# Sheet1.net
KiCad netlist of a schematic drawn in Altium Designer
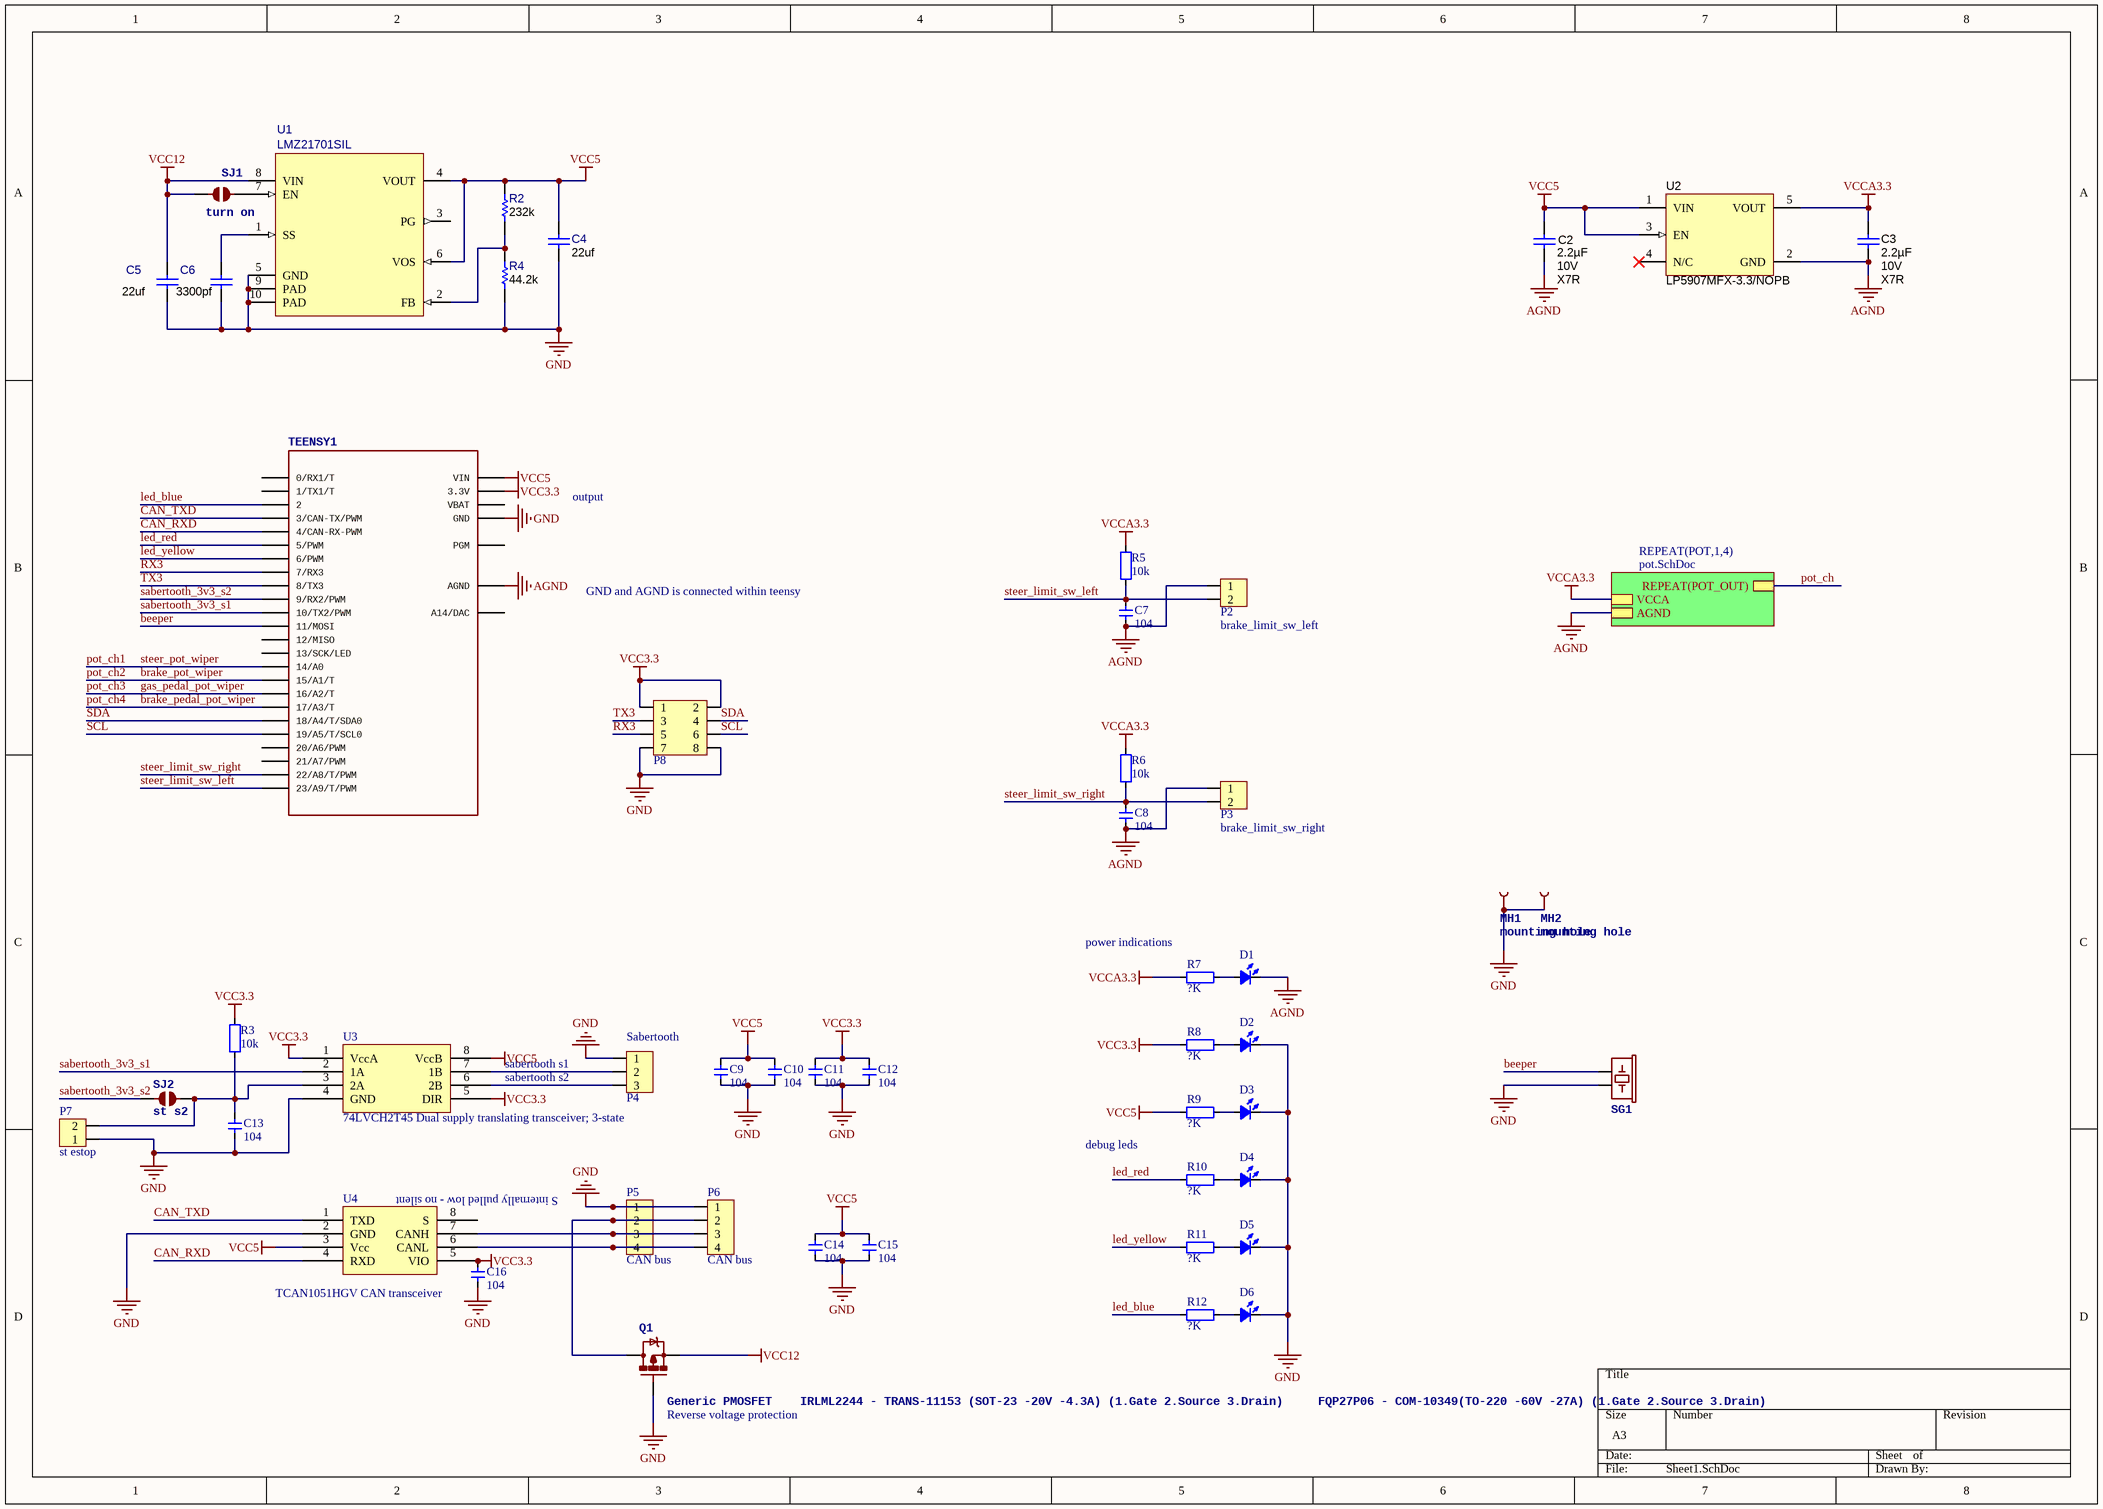
[diagram p0: Sheet1.SchDoc]

(export (version "E")
  (design (tool "Eeschema 10.0.6"))
  (components
    (comp (ref "C2")
      (value "GRM188R71A225KE15D")
      (footprint "PCB_PassiveCap:CAP_0603")
      (description "CAP, CERM, 2.2uF, 10V, +/-10%, X7R, 0603")
      (fields
        (field (name "VALUEDISPLAYED") "2.2µF")
        (field (name "MANUFACTURER") "MuRata")
        (field (name "VALUE2") "10V")
        (field (name "TEMPCO") "X7R")
        (field (name "PUBLISHER") "Texas Instruments")
      )
      (libsource (lib "Capacitor_Ceramic") (part "GRM188R71A225KE15D"))
    )
    (comp (ref "C3")
      (value "GRM188R71A225KE15D")
      (footprint "PCB_PassiveCap:CAP_0603")
      (description "CAP, CERM, 2.2 µF, 10 V, +/- 10%, X7R, 0603")
      (fields
        (field (name "VALUEDISPLAYED") "2.2µF")
        (field (name "MANUFACTURER") "MuRata")
        (field (name "VALUE2") "10V")
        (field (name "TEMPCO") "X7R")
        (field (name "PUBLISHER") "Texas Instruments")
      )
      (libsource (lib "Capacitor_Ceramic") (part "GRM188R71A225KE15D"))
    )
    (comp (ref "C4")
      (value "GRM188R71A225KE15D")
      (footprint "CAP_0805")
      (description "CAP, CERM, 2.2uF, 10V, +/-10%, X7R, 0603")
      (fields
        (field (name "VALUEDISPLAYED") "22uf")
        (field (name "MANUFACTURER") "MuRata")
        (field (name "PUBLISHER") "Texas Instruments")
      )
      (libsource (lib "Capacitor_Ceramic") (part "GRM188R71A225KE15D"))
    )
    (comp (ref "C5")
      (value "GRM155R71E822KA01D")
      (footprint "CAP_0805")
      (description "CAP, CERM, 8200pF, 25V, +/-10%, X7R, 0402")
      (fields
        (field (name "VALUEDISPLAYED") "22uf")
        (field (name "MANUFACTURER") "MuRata")
        (field (name "PUBLISHER") "Texas Instruments")
      )
      (libsource (lib "Capacitor_Ceramic") (part "GRM155R71E822KA01D"))
    )
    (comp (ref "C6")
      (value "GRM155R71E822KA01D")
      (footprint "PCB_PassiveCap:CAP_0603")
      (description "CAP, CERM, 8200pF, 25V, +/-10%, X7R, 0402")
      (fields
        (field (name "VALUEDISPLAYED") "3300pf")
        (field (name "MANUFACTURER") "MuRata")
        (field (name "PUBLISHER") "Texas Instruments")
      )
      (libsource (lib "Capacitor_Ceramic") (part "GRM155R71E822KA01D"))
    )
    (comp (ref "C7")
      (value "104")
      (footprint "PCB_PassiveCap:CAP_0603")
      (description "Capacitor")
      (fields (field (name "Comment") "Cap_0603"))
      (libsource (lib "SCH_Passive") (part "Cap_0603"))
    )
    (comp (ref "C8")
      (value "104")
      (footprint "PCB_PassiveCap:CAP_0603")
      (description "Capacitor")
      (fields (field (name "Comment") "Cap_0603"))
      (libsource (lib "SCH_Passive") (part "Cap_0603"))
    )
    (comp (ref "C9")
      (value "104")
      (footprint "PCB_PassiveCap:CAP_0603")
      (description "Capacitor")
      (fields (field (name "Comment") "Cap_0603"))
      (libsource (lib "SCH_Passive") (part "Cap_0603"))
    )
    (comp (ref "C10")
      (value "104")
      (footprint "PCB_PassiveCap:CAP_0603")
      (description "Capacitor")
      (fields (field (name "Comment") "Cap_0603"))
      (libsource (lib "SCH_Passive") (part "Cap_0603"))
    )
    (comp (ref "C11")
      (value "104")
      (footprint "PCB_PassiveCap:CAP_0603")
      (description "Capacitor")
      (fields (field (name "Comment") "Cap_0603"))
      (libsource (lib "SCH_Passive") (part "Cap_0603"))
    )
    (comp (ref "C12")
      (value "104")
      (footprint "PCB_PassiveCap:CAP_0603")
      (description "Capacitor")
      (fields (field (name "Comment") "Cap_0603"))
      (libsource (lib "SCH_Passive") (part "Cap_0603"))
    )
    (comp (ref "C13")
      (value "104")
      (footprint "PCB_PassiveCap:CAP_0603")
      (description "Capacitor")
      (fields (field (name "Comment") "Cap_0603"))
      (libsource (lib "SCH_Passive") (part "Cap_0603"))
    )
    (comp (ref "C14")
      (value "104")
      (footprint "PCB_PassiveCap:CAP_0603")
      (description "Capacitor")
      (fields (field (name "Comment") "Cap_0603"))
      (libsource (lib "SCH_Passive") (part "Cap_0603"))
    )
    (comp (ref "C15")
      (value "104")
      (footprint "PCB_PassiveCap:CAP_0603")
      (description "Capacitor")
      (fields (field (name "Comment") "Cap_0603"))
      (libsource (lib "SCH_Passive") (part "Cap_0603"))
    )
    (comp (ref "C16")
      (value "104")
      (footprint "PCB_PassiveCap:CAP_0603")
      (description "Capacitor")
      (fields (field (name "Comment") "Cap_0603"))
      (libsource (lib "SCH_Passive") (part "Cap_0603"))
    )
    (comp (ref "D1")
      (value "LED_0603")
      (footprint "PCB_ActiveLED:LED_0603_RED")
      (description "LED")
      (libsource (lib "SCH_Active") (part "LED_0603"))
    )
    (comp (ref "D2")
      (value "LED_0603")
      (footprint "PCB_ActiveLED:LED_0603_RED")
      (description "LED")
      (libsource (lib "SCH_Active") (part "LED_0603"))
    )
    (comp (ref "D3")
      (value "LED_0603")
      (footprint "PCB_ActiveLED:LED_0603_RED")
      (description "LED")
      (libsource (lib "SCH_Active") (part "LED_0603"))
    )
    (comp (ref "D4")
      (value "LED_0603")
      (footprint "PCB_ActiveLED:LED_0603_RED")
      (description "LED")
      (libsource (lib "SCH_Active") (part "LED_0603"))
    )
    (comp (ref "D5")
      (value "LED_0603")
      (footprint "PCB_ActiveLED:LED_0603_RED")
      (description "LED")
      (libsource (lib "SCH_Active") (part "LED_0603"))
    )
    (comp (ref "D6")
      (value "LED_0603")
      (footprint "PCB_ActiveLED:LED_0603_RED")
      (description "LED")
      (libsource (lib "SCH_Active") (part "LED_0603"))
    )
    (comp (ref "MH1")
      (value "mounting hole")
      (footprint "M3 hole")
      (libsource (lib "SparkFun-Passives") (part "TEST-POINT2"))
    )
    (comp (ref "MH2")
      (value "mounting hole")
      (footprint "M3 hole")
      (libsource (lib "SparkFun-Passives") (part "TEST-POINT2"))
    )
    (comp (ref "P2")
      (value "brake_limit_sw_left")
      (footprint "COMBICON PTSA 2")
      (description "Header")
      (libsource (lib "") (part "HDR1x2_2.54_1"))
    )
    (comp (ref "P3")
      (value "brake_limit_sw_right")
      (footprint "COMBICON PTSA 2")
      (description "Header")
      (libsource (lib "") (part "HDR1x2_2.54_1"))
    )
    (comp (ref "P4")
      (value "Sabertooth")
      (footprint "COMBICON PTSA 3")
      (description "Header")
      (libsource (lib "SCH_ConnectorHDR") (part "HDR1x3_2.54"))
    )
    (comp (ref "P5")
      (value "CAN bus")
      (footprint "COMBICON PTSA 4")
      (description "Header")
      (libsource (lib "SCH_ConnectorHDR") (part "HDR1x4_2.54"))
    )
    (comp (ref "P6")
      (value "CAN bus")
      (footprint "COMBICON PTSA 4")
      (description "Header")
      (libsource (lib "SCH_ConnectorHDR") (part "HDR1x4_2.54"))
    )
    (comp (ref "P7")
      (value "st estop")
      (footprint "COMBICON PTSA 2")
      (description "Header")
      (libsource (lib "SCH_ConnectorHDR") (part "HDR1x2_2.54"))
    )
    (comp (ref "P8")
      (value "HDR2x4_2.54")
      (footprint "PCB_ConnectorHDR:HDR2X4_2.54_90")
      (description "Header")
      (libsource (lib "SCH_ConnectorHDR") (part "HDR2x4_2.54"))
    )
    (comp (ref "Q1")
      (value "Generic PMOSFET    IRLML2244 - TRANS-11153 (SOT-23 -20V -4.3A) (1.Gate 2.Source 3.Drain)     FQP27P06 - COM-10349(TO-220 -60V -27A) (1.Gate 2.Source 3.Drain)")
      (footprint "SOT23-3")
      (libsource (lib "SparkFun-DiscreteSemi") (part "MOSFET-PCHANNEL"))
    )
    (comp (ref "R2")
      (value "232k")
      (footprint "PCB_PassiveRes:RES_0603")
      (description "RES, 35.7k ohm, 1%, 0.063W, 0402")
      (fields
        (field (name "PARTNUMBER") "CRCW040235K7FKED")
        (field (name "MANUFACTURER") "Vishay-Dale")
        (field (name "PUBLISHER") "Texas Instruments")
      )
      (libsource (lib "Resistor_0402") (part "CRCW040235K7FKED"))
    )
    (comp (ref "R3")
      (value "10k")
      (footprint "PCB_PassiveRes:RES_0603")
      (description "Resistor")
      (fields (field (name "Comment") "Res_0603"))
      (libsource (lib "") (part "Res_0603_1"))
    )
    (comp (ref "R4")
      (value "44.2k")
      (footprint "PCB_PassiveRes:RES_0603")
      (description "RES, 6.81k ohm, 1%, 0.063W, 0402")
      (fields
        (field (name "PARTNUMBER") "CRCW04026K81FKED")
        (field (name "MANUFACTURER") "Vishay-Dale")
        (field (name "PUBLISHER") "Texas Instruments")
      )
      (libsource (lib "Resistor_0402") (part "CRCW04026K81FKED"))
    )
    (comp (ref "R5")
      (value "10k")
      (footprint "PCB_PassiveRes:RES_0603")
      (description "Resistor")
      (fields (field (name "Comment") "Res_0603"))
      (libsource (lib "") (part "Res_0603_1"))
    )
    (comp (ref "R6")
      (value "10k")
      (footprint "PCB_PassiveRes:RES_0603")
      (description "Resistor")
      (fields (field (name "Comment") "Res_0603"))
      (libsource (lib "") (part "Res_0603_1"))
    )
    (comp (ref "R7")
      (value "?K")
      (footprint "PCB_PassiveRes:RES_0603")
      (description "Resistor")
      (fields (field (name "Comment") "Res_0603"))
      (libsource (lib "SCH_Passive") (part "Res_0603"))
    )
    (comp (ref "R8")
      (value "?K")
      (footprint "PCB_PassiveRes:RES_0603")
      (description "Resistor")
      (fields (field (name "Comment") "Res_0603"))
      (libsource (lib "SCH_Passive") (part "Res_0603"))
    )
    (comp (ref "R9")
      (value "?K")
      (footprint "PCB_PassiveRes:RES_0603")
      (description "Resistor")
      (fields (field (name "Comment") "Res_0603"))
      (libsource (lib "SCH_Passive") (part "Res_0603"))
    )
    (comp (ref "R10")
      (value "?K")
      (footprint "PCB_PassiveRes:RES_0603")
      (description "Resistor")
      (fields (field (name "Comment") "Res_0603"))
      (libsource (lib "SCH_Passive") (part "Res_0603"))
    )
    (comp (ref "R11")
      (value "?K")
      (footprint "PCB_PassiveRes:RES_0603")
      (description "Resistor")
      (fields (field (name "Comment") "Res_0603"))
      (libsource (lib "SCH_Passive") (part "Res_0603"))
    )
    (comp (ref "R12")
      (value "?K")
      (footprint "PCB_PassiveRes:RES_0603")
      (description "Resistor")
      (fields (field (name "Comment") "Res_0603"))
      (libsource (lib "SCH_Passive") (part "Res_0603"))
    )
    (comp (ref "SG1")
      (value "Buzzer 12mmSpark Fun Electronics SKU : Comp-Buzzer")
      (footprint "Buzzer_5x5")
      (libsource (lib "SparkFun-Electromechanical") (part "BUZZERPTH"))
    )
    (comp (ref "SJ1")
      (value "turn on")
      (footprint "HDR1X2_2.54_180")
      (libsource (lib "SparkFun-Passives") (part "JUMPER-PAD-2-NOROUND"))
    )
    (comp (ref "SJ2")
      (value "st s2")
      (footprint "PAD-JUMPER-2-NO_YES_SILK")
      (libsource (lib "SparkFun-Passives") (part "JUMPER-PAD-2-NOROUND"))
    )
    (comp (ref "TEENSY1")
      (value "Footprint for Teensy 3.1 board using all pin connections on the outer perimeter")
      (footprint "TEENSY_3.1_BASIC_FIXED")
      (libsource (lib "Teensy_3_Series_Board_v1.0") (part "TEENSY_3.1_BASIC"))
    )
    (comp (ref "U1")
      (value "LMZ21701SIL")
      (footprint "LMZ21701SIL")
      (description "1A SIMPLE SWITCHER Nano Module with 17V Maximum Input Voltage, SIL0008E")
      (fields
        (field (name "MANUFACTURER") "Texas Instruments")
        (field (name "SYMBOLCREATOR") "a0411947")
        (field (name "PUBLISHER") "Texas Instruments")
      )
      (libsource (lib "TI_Pre_RTM") (part "LMZ21701SIL"))
    )
    (comp (ref "U2")
      (value "LP5907MFX-3.3/NOPB")
      (footprint "DBV0005A_N")
      (fields
        (field (name "MANUFACTURER") "Texas Instruments")
        (field (name "PUBLISHER") "Texas Instruments")
        (field (name "SYMBOLCREATOR") "a0799628")
      )
      (libsource (lib "ISE4022_TIDA-00314") (part "LP5907MFX-3.3/NOPB"))
    )
    (comp (ref "U3")
      (value "74LVCH2T45 Dual supply translating transceiver; 3-state")
      (footprint "SOP65P490X110-8N")
      (libsource (lib "robocart") (part "74LVCH2T45"))
    )
    (comp (ref "U4")
      (value "TCAN1051HGV CAN transceiver")
      (footprint "SOIC_E200_8")
      (libsource (lib "robocart") (part "TCAN1051HGV"))
    )
  )
  (nets
    (net (code "1") (name "/CAN_RXD") (class "Default")
      (node (ref "TEENSY1") (pin "4") (pinfunction "4/CAN-RX-PWM_4") (pintype "passive"))
      (node (ref "U4") (pin "4") (pinfunction "RXD_4") (pintype "passive"))
    )
    (net (code "2") (name "/CAN_TXD") (class "Default")
      (node (ref "TEENSY1") (pin "3") (pinfunction "3/CAN-TX/PWM_3") (pintype "passive"))
      (node (ref "U4") (pin "1") (pinfunction "TXD_1") (pintype "passive"))
    )
    (net (code "3") (name "/RX3") (class "Default")
      (node (ref "P8") (pin "5") (pinfunction "5_5") (pintype "passive"))
      (node (ref "TEENSY1") (pin "7") (pinfunction "7/RX3_7") (pintype "passive"))
    )
    (net (code "4") (name "/SCL") (class "Default")
      (node (ref "P8") (pin "6") (pinfunction "6_6") (pintype "passive"))
      (node (ref "TEENSY1") (pin "19/A5") (pinfunction "19/A5/T/SCL0_19/A5") (pintype "passive"))
    )
    (net (code "5") (name "/SDA") (class "Default")
      (node (ref "P8") (pin "4") (pinfunction "4_4") (pintype "passive"))
      (node (ref "TEENSY1") (pin "18/A4") (pinfunction "18/A4/T/SDA0_18/A4") (pintype "passive"))
    )
    (net (code "6") (name "/TX3") (class "Default")
      (node (ref "P8") (pin "3") (pinfunction "3_3") (pintype "passive"))
      (node (ref "TEENSY1") (pin "8") (pinfunction "8/TX3_8") (pintype "passive"))
    )
    (net (code "7") (name "/beeper") (class "Default")
      (node (ref "SG1") (pin "+") (pinfunction "1_+") (pintype "passive"))
      (node (ref "TEENSY1") (pin "11") (pinfunction "11/MOSI_11") (pintype "passive"))
    )
    (net (code "8") (name "/brake_pedal_pot_wiper") (class "Default")
      (node (ref "TEENSY1") (pin "17/A3") (pinfunction "17/A3/T_17/A3") (pintype "passive"))
    )
    (net (code "9") (name "/brake_pot_wiper") (class "Default")
      (node (ref "TEENSY1") (pin "15/A1") (pinfunction "15/A1/T_15/A1") (pintype "passive"))
    )
    (net (code "10") (name "/gas_pedal_pot_wiper") (class "Default")
      (node (ref "TEENSY1") (pin "16/A2") (pinfunction "16/A2/T_16/A2") (pintype "passive"))
    )
    (net (code "11") (name "/led_blue") (class "Default")
      (node (ref "R12") (pin "1") (pinfunction "1_1") (pintype "passive"))
      (node (ref "TEENSY1") (pin "2") (pinfunction "2_2") (pintype "passive"))
    )
    (net (code "12") (name "/led_red") (class "Default")
      (node (ref "R10") (pin "1") (pinfunction "1_1") (pintype "passive"))
      (node (ref "TEENSY1") (pin "5") (pinfunction "5/PWM_5") (pintype "passive"))
    )
    (net (code "13") (name "/led_yellow") (class "Default")
      (node (ref "R11") (pin "1") (pinfunction "1_1") (pintype "passive"))
      (node (ref "TEENSY1") (pin "6") (pinfunction "6/PWM_6") (pintype "passive"))
    )
    (net (code "15") (name "/pot_ch1") (class "Default")
      (node (ref "TEENSY1") (pin "14/A0") (pinfunction "14/A0_14/A0") (pintype "passive"))
    )
    (net (code "16") (name "/sabertooth_3v3_s1") (class "Default")
      (node (ref "TEENSY1") (pin "10") (pinfunction "10/TX2/PWM_10") (pintype "passive"))
      (node (ref "U3") (pin "2") (pinfunction "1A_2") (pintype "passive"))
    )
    (net (code "17") (name "/sabertooth_3v3_s2") (class "Default")
      (node (ref "SJ2") (pin "1") (pinfunction "1_1") (pintype "passive"))
      (node (ref "TEENSY1") (pin "9") (pinfunction "9/RX2/PWM_9") (pintype "passive"))
    )
    (net (code "18") (name "/steer_limit_sw_left") (class "Default")
      (node (ref "C7") (pin "2") (pinfunction "2_2") (pintype "passive"))
      (node (ref "P2") (pin "2") (pinfunction "2_2") (pintype "passive"))
      (node (ref "R5") (pin "1") (pinfunction "1_1") (pintype "passive"))
      (node (ref "TEENSY1") (pin "23/A9") (pinfunction "23/A9/T/PWM_23/A9") (pintype "passive"))
    )
    (net (code "19") (name "/steer_limit_sw_right") (class "Default")
      (node (ref "C8") (pin "2") (pinfunction "2_2") (pintype "passive"))
      (node (ref "P3") (pin "2") (pinfunction "2_2") (pintype "passive"))
      (node (ref "R6") (pin "1") (pinfunction "1_1") (pintype "passive"))
      (node (ref "TEENSY1") (pin "22/A8") (pinfunction "22/A8/T/PWM_22/A8") (pintype "passive"))
    )
    (net (code "20") (name "AGND") (class "Default")
      (node (ref "C2") (pin "1") (pinfunction "1_1") (pintype "passive"))
      (node (ref "C3") (pin "1") (pinfunction "1_1") (pintype "passive"))
      (node (ref "C7") (pin "1") (pinfunction "1_1") (pintype "passive"))
      (node (ref "C8") (pin "1") (pinfunction "1_1") (pintype "passive"))
      (node (ref "D1") (pin "2") (pinfunction "K_2") (pintype "passive"))
      (node (ref "P2") (pin "1") (pinfunction "1_1") (pintype "passive"))
      (node (ref "P3") (pin "1") (pinfunction "1_1") (pintype "passive"))
      (node (ref "TEENSY1") (pin "AGND") (pinfunction "AGND_AGND") (pintype "power_in"))
      (node (ref "U2") (pin "2") (pinfunction "GND_2") (pintype "power_in"))
    )
    (net (code "21") (name "GND") (class "Default")
      (node (ref "C10") (pin "1") (pinfunction "1_1") (pintype "passive"))
      (node (ref "C11") (pin "1") (pinfunction "1_1") (pintype "passive"))
      (node (ref "C12") (pin "1") (pinfunction "1_1") (pintype "passive"))
      (node (ref "C13") (pin "1") (pinfunction "1_1") (pintype "passive"))
      (node (ref "C14") (pin "1") (pinfunction "1_1") (pintype "passive"))
      (node (ref "C15") (pin "1") (pinfunction "1_1") (pintype "passive"))
      (node (ref "C16") (pin "1") (pinfunction "1_1") (pintype "passive"))
      (node (ref "C4") (pin "2") (pinfunction "2_2") (pintype "passive"))
      (node (ref "C5") (pin "2") (pinfunction "2_2") (pintype "passive"))
      (node (ref "C6") (pin "2") (pinfunction "2_2") (pintype "passive"))
      (node (ref "C9") (pin "1") (pinfunction "1_1") (pintype "passive"))
      (node (ref "D2") (pin "2") (pinfunction "K_2") (pintype "passive"))
      (node (ref "D3") (pin "2") (pinfunction "K_2") (pintype "passive"))
      (node (ref "D4") (pin "2") (pinfunction "K_2") (pintype "passive"))
      (node (ref "D5") (pin "2") (pinfunction "K_2") (pintype "passive"))
      (node (ref "D6") (pin "2") (pinfunction "K_2") (pintype "passive"))
      (node (ref "MH1") (pin "P$1") (pinfunction "1_P$1") (pintype "passive"))
      (node (ref "MH2") (pin "P$1") (pinfunction "1_P$1") (pintype "passive"))
      (node (ref "P4") (pin "1") (pinfunction "1_1") (pintype "passive"))
      (node (ref "P5") (pin "1") (pinfunction "1_1") (pintype "passive"))
      (node (ref "P6") (pin "1") (pinfunction "1_1") (pintype "passive"))
      (node (ref "P7") (pin "1") (pinfunction "1_1") (pintype "passive"))
      (node (ref "P8") (pin "7") (pinfunction "7_7") (pintype "passive"))
      (node (ref "P8") (pin "8") (pinfunction "8_8") (pintype "passive"))
      (node (ref "Q1") (pin "1") (pinfunction "G_1") (pintype "passive"))
      (node (ref "R4") (pin "1") (pinfunction "1_1") (pintype "passive"))
      (node (ref "SG1") (pin "-") (pinfunction "2_-") (pintype "passive"))
      (node (ref "TEENSY1") (pin "GND_GND1") (pinfunction "GND_GND_GND1") (pintype "power_in"))
      (node (ref "U1") (pin "10") (pinfunction "PAD_10") (pintype "power_in"))
      (node (ref "U1") (pin "5") (pinfunction "GND_5") (pintype "power_in"))
      (node (ref "U1") (pin "9") (pinfunction "PAD_9") (pintype "power_in"))
      (node (ref "U3") (pin "4") (pinfunction "GND_4") (pintype "passive"))
      (node (ref "U4") (pin "2") (pinfunction "GND_2") (pintype "passive"))
    )
    (net (code "22") (name "Net-(D1-A)") (class "Default")
      (node (ref "D1") (pin "1") (pinfunction "A_1") (pintype "passive"))
      (node (ref "R7") (pin "2") (pinfunction "2_2") (pintype "passive"))
    )
    (net (code "23") (name "Net-(D2-A)") (class "Default")
      (node (ref "D2") (pin "1") (pinfunction "A_1") (pintype "passive"))
      (node (ref "R8") (pin "2") (pinfunction "2_2") (pintype "passive"))
    )
    (net (code "24") (name "Net-(D3-A)") (class "Default")
      (node (ref "D3") (pin "1") (pinfunction "A_1") (pintype "passive"))
      (node (ref "R9") (pin "2") (pinfunction "2_2") (pintype "passive"))
    )
    (net (code "25") (name "Net-(D4-A)") (class "Default")
      (node (ref "D4") (pin "1") (pinfunction "A_1") (pintype "passive"))
      (node (ref "R10") (pin "2") (pinfunction "2_2") (pintype "passive"))
    )
    (net (code "26") (name "Net-(D5-A)") (class "Default")
      (node (ref "D5") (pin "1") (pinfunction "A_1") (pintype "passive"))
      (node (ref "R11") (pin "2") (pinfunction "2_2") (pintype "passive"))
    )
    (net (code "27") (name "Net-(D6-A)") (class "Default")
      (node (ref "D6") (pin "1") (pinfunction "A_1") (pintype "passive"))
      (node (ref "R12") (pin "2") (pinfunction "2_2") (pintype "passive"))
    )
    (net (code "28") (name "Net-(Q1-D)") (class "Default")
      (node (ref "P5") (pin "2") (pinfunction "2_2") (pintype "passive"))
      (node (ref "P6") (pin "2") (pinfunction "2_2") (pintype "passive"))
      (node (ref "Q1") (pin "3") (pinfunction "D_3") (pintype "passive"))
    )
    (net (code "29") (name "Net-(U1-EN)") (class "Default")
      (node (ref "SJ1") (pin "2") (pinfunction "2_2") (pintype "passive"))
      (node (ref "U1") (pin "7") (pinfunction "EN_7") (pintype "input"))
    )
    (net (code "30") (name "Net-(U1-FB)") (class "Default")
      (node (ref "R2") (pin "1") (pinfunction "1_1") (pintype "passive"))
      (node (ref "R4") (pin "2") (pinfunction "2_2") (pintype "passive"))
      (node (ref "U1") (pin "2") (pinfunction "FB_2") (pintype "input"))
    )
    (net (code "31") (name "Net-(U1-SS)") (class "Default")
      (node (ref "C6") (pin "1") (pinfunction "1_1") (pintype "passive"))
      (node (ref "U1") (pin "1") (pinfunction "SS_1") (pintype "input"))
    )
    (net (code "32") (name "Net-(U3-1B)") (class "Default")
      (node (ref "P4") (pin "2") (pinfunction "2_2") (pintype "passive"))
      (node (ref "U3") (pin "7") (pinfunction "1B_7") (pintype "passive"))
    )
    (net (code "33") (name "Net-(U3-2A)") (class "Default")
      (node (ref "C13") (pin "2") (pinfunction "2_2") (pintype "passive"))
      (node (ref "P7") (pin "2") (pinfunction "2_2") (pintype "passive"))
      (node (ref "R3") (pin "1") (pinfunction "1_1") (pintype "passive"))
      (node (ref "SJ2") (pin "2") (pinfunction "2_2") (pintype "passive"))
      (node (ref "U3") (pin "3") (pinfunction "2A_3") (pintype "passive"))
    )
    (net (code "34") (name "Net-(U3-2B)") (class "Default")
      (node (ref "P4") (pin "3") (pinfunction "3_3") (pintype "passive"))
      (node (ref "U3") (pin "6") (pinfunction "2B_6") (pintype "passive"))
    )
    (net (code "35") (name "Net-(U4-CANH)") (class "Default")
      (node (ref "P5") (pin "3") (pinfunction "3_3") (pintype "passive"))
      (node (ref "P6") (pin "3") (pinfunction "3_3") (pintype "passive"))
      (node (ref "U4") (pin "7") (pinfunction "CANH_7") (pintype "passive"))
    )
    (net (code "36") (name "Net-(U4-CANL)") (class "Default")
      (node (ref "P5") (pin "4") (pinfunction "4_4") (pintype "passive"))
      (node (ref "P6") (pin "4") (pinfunction "4_4") (pintype "passive"))
      (node (ref "U4") (pin "6") (pinfunction "CANL_6") (pintype "passive"))
    )
    (net (code "37") (name "VCC3.3") (class "Default")
      (node (ref "C11") (pin "2") (pinfunction "2_2") (pintype "passive"))
      (node (ref "C12") (pin "2") (pinfunction "2_2") (pintype "passive"))
      (node (ref "C16") (pin "2") (pinfunction "2_2") (pintype "passive"))
      (node (ref "P8") (pin "1") (pinfunction "1_1") (pintype "passive"))
      (node (ref "P8") (pin "2") (pinfunction "2_2") (pintype "passive"))
      (node (ref "R3") (pin "2") (pinfunction "2_2") (pintype "passive"))
      (node (ref "R8") (pin "1") (pinfunction "1_1") (pintype "passive"))
      (node (ref "TEENSY1") (pin "3.3V_3.3V1") (pinfunction "3.3V_3.3V_3.3V1") (pintype "power_in"))
      (node (ref "U3") (pin "1") (pinfunction "VccA_1") (pintype "passive"))
      (node (ref "U3") (pin "5") (pinfunction "DIR_5") (pintype "passive"))
      (node (ref "U4") (pin "5") (pinfunction "VIO_5") (pintype "passive"))
    )
    (net (code "38") (name "VCC5") (class "Default")
      (node (ref "C10") (pin "2") (pinfunction "2_2") (pintype "passive"))
      (node (ref "C14") (pin "2") (pinfunction "2_2") (pintype "passive"))
      (node (ref "C15") (pin "2") (pinfunction "2_2") (pintype "passive"))
      (node (ref "C2") (pin "2") (pinfunction "2_2") (pintype "passive"))
      (node (ref "C4") (pin "1") (pinfunction "1_1") (pintype "passive"))
      (node (ref "C9") (pin "2") (pinfunction "2_2") (pintype "passive"))
      (node (ref "R2") (pin "2") (pinfunction "2_2") (pintype "passive"))
      (node (ref "R9") (pin "1") (pinfunction "1_1") (pintype "passive"))
      (node (ref "TEENSY1") (pin "VIN") (pinfunction "VIN_VIN") (pintype "power_in"))
      (node (ref "U1") (pin "4") (pinfunction "VOUT_4") (pintype "power_in"))
      (node (ref "U1") (pin "6") (pinfunction "VOS_6") (pintype "input"))
      (node (ref "U2") (pin "1") (pinfunction "VIN_1") (pintype "power_in"))
      (node (ref "U2") (pin "3") (pinfunction "EN_3") (pintype "input"))
      (node (ref "U3") (pin "8") (pinfunction "VccB_8") (pintype "passive"))
      (node (ref "U4") (pin "3") (pinfunction "Vcc_3") (pintype "passive"))
    )
    (net (code "39") (name "VCC12") (class "Default")
      (node (ref "C5") (pin "1") (pinfunction "1_1") (pintype "passive"))
      (node (ref "Q1") (pin "2") (pinfunction "S_2") (pintype "passive"))
      (node (ref "SJ1") (pin "1") (pinfunction "1_1") (pintype "passive"))
      (node (ref "U1") (pin "8") (pinfunction "VIN_8") (pintype "power_in"))
    )
    (net (code "40") (name "VCCA3.3") (class "Default")
      (node (ref "C3") (pin "2") (pinfunction "2_2") (pintype "passive"))
      (node (ref "R5") (pin "2") (pinfunction "2_2") (pintype "passive"))
      (node (ref "R6") (pin "2") (pinfunction "2_2") (pintype "passive"))
      (node (ref "R7") (pin "1") (pinfunction "1_1") (pintype "passive"))
      (node (ref "U2") (pin "5") (pinfunction "VOUT_5") (pintype "power_in"))
    )
    (net (code "41") (name "unconnected-(TEENSY1-0{slash}RX1{slash}T-Pad0)") (class "Default")
      (node (ref "TEENSY1") (pin "0") (pinfunction "0/RX1/T_0") (pintype "passive"))
    )
    (net (code "42") (name "unconnected-(TEENSY1-1{slash}TX1{slash}T-Pad1)") (class "Default")
      (node (ref "TEENSY1") (pin "1") (pinfunction "1/TX1/T_1") (pintype "passive"))
    )
    (net (code "43") (name "unconnected-(TEENSY1-12{slash}MISO-Pad12)") (class "Default")
      (node (ref "TEENSY1") (pin "12") (pinfunction "12/MISO_12") (pintype "passive"))
    )
    (net (code "44") (name "unconnected-(TEENSY1-13{slash}SCK{slash}LED-Pad13)") (class "Default")
      (node (ref "TEENSY1") (pin "13") (pinfunction "13/SCK/LED_13") (pintype "passive"))
    )
    (net (code "45") (name "unconnected-(TEENSY1-20{slash}A6{slash}PWM-Pad20{slash}A6)") (class "Default")
      (node (ref "TEENSY1") (pin "20/A6") (pinfunction "20/A6/PWM_20/A6") (pintype "passive"))
    )
    (net (code "46") (name "unconnected-(TEENSY1-21{slash}A7{slash}PWM-Pad21{slash}A7)") (class "Default")
      (node (ref "TEENSY1") (pin "21/A7") (pinfunction "21/A7/PWM_21/A7") (pintype "passive"))
    )
    (net (code "47") (name "unconnected-(TEENSY1-A14{slash}DAC-PadA14)") (class "Default")
      (node (ref "TEENSY1") (pin "A14") (pinfunction "A14/DAC_A14") (pintype "passive"))
    )
    (net (code "48") (name "unconnected-(TEENSY1-PadPGM)") (class "Default")
      (node (ref "TEENSY1") (pin "PGM") (pinfunction "PGM_PGM") (pintype "passive"))
    )
    (net (code "49") (name "unconnected-(TEENSY1-PadVBAT)") (class "Default")
      (node (ref "TEENSY1") (pin "VBAT") (pinfunction "VBAT_VBAT") (pintype "power_in"))
    )
    (net (code "50") (name "unconnected-(U1-PG-Pad3)") (class "Default")
      (node (ref "U1") (pin "3") (pinfunction "PG_3") (pintype "output"))
    )
    (net (code "51") (name "unconnected-(U2-N{slash}C-Pad4)") (class "Default")
      (node (ref "U2") (pin "4") (pinfunction "N/C_4") (pintype "passive+no_connect"))
    )
    (net (code "52") (name "unconnected-(U4-S-Pad8)") (class "Default")
      (node (ref "U4") (pin "8") (pinfunction "S_8") (pintype "passive"))
    )
  )
)
